# demod-breakout.net
KiCad netlist of a schematic drawn in EAGLE
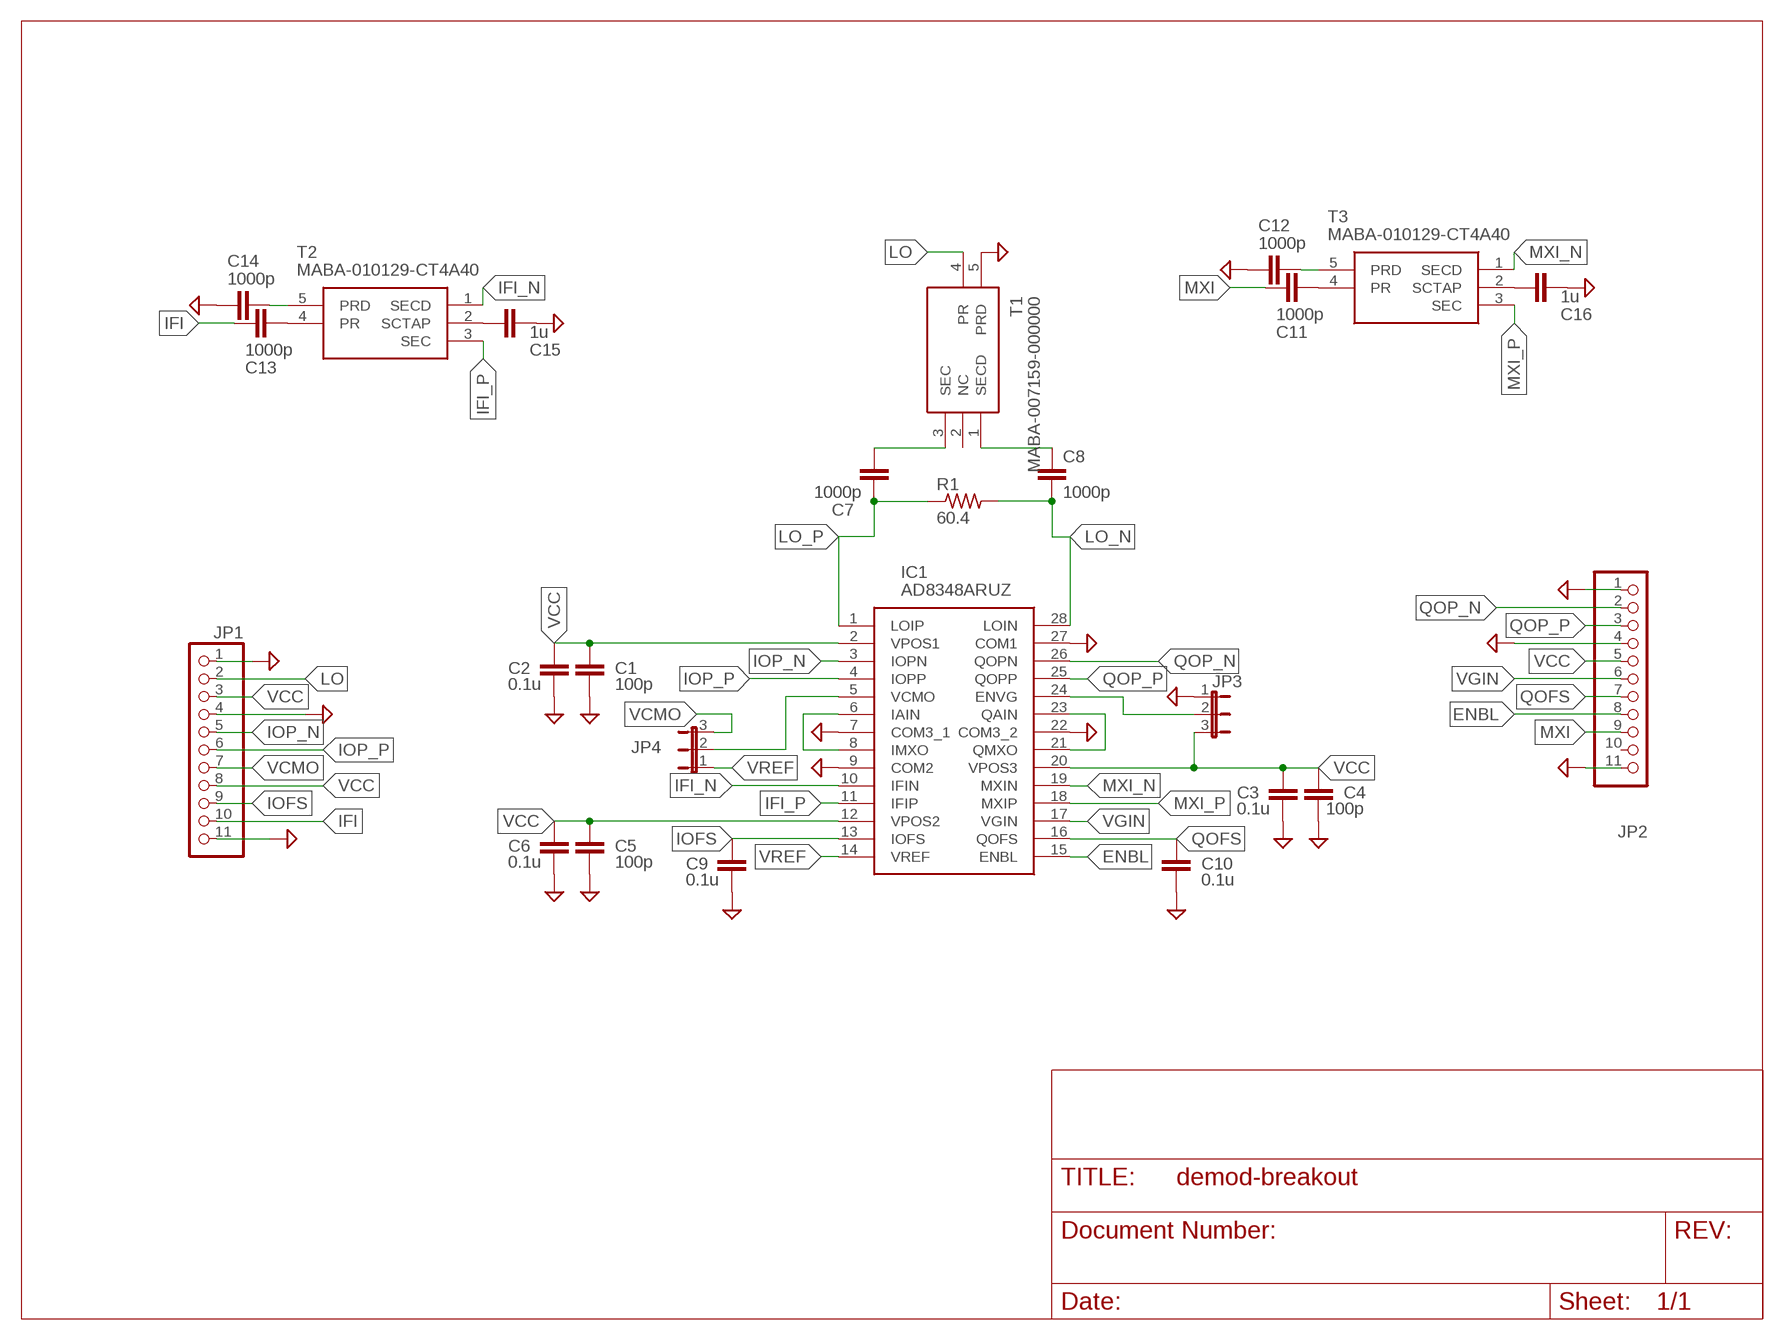
[diagram p0: schematic, sheet 1]

(export (version "E")
  (design (tool "Eeschema 10.0.6"))
  (components
    (comp (ref "C1")
      (value "100p")
      (footprint "eagle-import:C0402")
      (libsource (lib "eagle-import") (part "C-EUC0402"))
    )
    (comp (ref "C2")
      (value "0.1u")
      (footprint "eagle-import:C0402")
      (libsource (lib "eagle-import") (part "C-EUC0402"))
    )
    (comp (ref "C3")
      (value "0.1u")
      (footprint "eagle-import:C0402")
      (libsource (lib "eagle-import") (part "C-EUC0402"))
    )
    (comp (ref "C4")
      (value "100p")
      (footprint "eagle-import:C0402")
      (libsource (lib "eagle-import") (part "C-EUC0402"))
    )
    (comp (ref "C5")
      (value "100p")
      (footprint "eagle-import:C0402")
      (libsource (lib "eagle-import") (part "C-EUC0402"))
    )
    (comp (ref "C6")
      (value "0.1u")
      (footprint "eagle-import:C0402")
      (libsource (lib "eagle-import") (part "C-EUC0402"))
    )
    (comp (ref "C7")
      (value "1000p")
      (footprint "eagle-import:C0402")
      (libsource (lib "eagle-import") (part "C-EUC0402"))
    )
    (comp (ref "C8")
      (value "1000p")
      (footprint "eagle-import:C0402")
      (libsource (lib "eagle-import") (part "C-EUC0402"))
    )
    (comp (ref "C9")
      (value "0.1u")
      (footprint "eagle-import:C0402")
      (libsource (lib "eagle-import") (part "C-EUC0402"))
    )
    (comp (ref "C10")
      (value "0.1u")
      (footprint "eagle-import:C0402")
      (libsource (lib "eagle-import") (part "C-EUC0402"))
    )
    (comp (ref "C11")
      (value "1000p")
      (footprint "eagle-import:C0402")
      (libsource (lib "eagle-import") (part "C-EUC0402"))
    )
    (comp (ref "C12")
      (value "1000p")
      (footprint "eagle-import:C0402")
      (libsource (lib "eagle-import") (part "C-EUC0402"))
    )
    (comp (ref "C13")
      (value "1000p")
      (footprint "eagle-import:C0402")
      (libsource (lib "eagle-import") (part "C-EUC0402"))
    )
    (comp (ref "C14")
      (value "1000p")
      (footprint "eagle-import:C0402")
      (libsource (lib "eagle-import") (part "C-EUC0402"))
    )
    (comp (ref "C15")
      (value "1u")
      (footprint "eagle-import:C0603")
      (libsource (lib "eagle-import") (part "C-EUC0603"))
    )
    (comp (ref "C16")
      (value "1u")
      (footprint "eagle-import:C0603")
      (libsource (lib "eagle-import") (part "C-EUC0603"))
    )
    (comp (ref "IC1")
      (value "AD8348ARUZ")
      (footprint "eagle-import:SOP65P640X120-28N")
      (fields (field (name "MOUSER_PART_NUMBER") "584-AD8348ARUZ"))
      (libsource (lib "eagle-import") (part "AD8348ARUZ"))
    )
    (comp (ref "JP1")
      (value "PINHD-1X11")
      (footprint "eagle-import:1X11")
      (libsource (lib "eagle-import") (part "PINHD-1X11"))
    )
    (comp (ref "JP2")
      (value "PINHD-1X11")
      (footprint "eagle-import:1X11")
      (libsource (lib "eagle-import") (part "PINHD-1X11"))
    )
    (comp (ref "JP3")
      (value "VGA")
      (footprint "eagle-import:JP2")
      (libsource (lib "eagle-import") (part "JP2"))
    )
    (comp (ref "JP4")
      (value "VCMO")
      (footprint "eagle-import:JP2")
      (libsource (lib "eagle-import") (part "JP2"))
    )
    (comp (ref "R1")
      (value "60.4")
      (footprint "eagle-import:R0402")
      (libsource (lib "eagle-import") (part "R-US_R0402"))
    )
    (comp (ref "T1")
      (value "MABA-007159-000000")
      (footprint "eagle-import:E_SERIES_1")
      (fields (field (name "MOUSER_PART_NUMBER") "937-MABA007159000000"))
      (libsource (lib "eagle-import") (part "MABA-007159-000000"))
    )
    (comp (ref "T2")
      (value "MABA-010129-CT4A40")
      (footprint "eagle-import:MABA010129CT4A40")
      (fields (field (name "MOUSER_PART_NUMBER") "937-MABA010129CT4A40"))
      (libsource (lib "eagle-import") (part "MABA-010129-CT4A40"))
    )
    (comp (ref "T3")
      (value "MABA-010129-CT4A40")
      (footprint "eagle-import:MABA010129CT4A40")
      (fields (field (name "MOUSER_PART_NUMBER") "937-MABA010129CT4A40"))
      (libsource (lib "eagle-import") (part "MABA-010129-CT4A40"))
    )
  )
  (nets
    (net (code "1") (name "ENBL") (class "Default")
      (node (ref "IC1") (pin "15") (pinfunction "ENBL_15") (pintype "bidirectional"))
      (node (ref "JP2") (pin "8") (pinfunction "8_8") (pintype "passive"))
    )
    (net (code "2") (name "GND") (class "Default")
      (node (ref "C1") (pin "2") (pinfunction "2_2") (pintype "passive"))
      (node (ref "C10") (pin "2") (pinfunction "2_2") (pintype "passive"))
      (node (ref "C12") (pin "2") (pinfunction "2_2") (pintype "passive"))
      (node (ref "C14") (pin "2") (pinfunction "2_2") (pintype "passive"))
      (node (ref "C15") (pin "2") (pinfunction "2_2") (pintype "passive"))
      (node (ref "C16") (pin "2") (pinfunction "2_2") (pintype "passive"))
      (node (ref "C2") (pin "2") (pinfunction "2_2") (pintype "passive"))
      (node (ref "C3") (pin "2") (pinfunction "2_2") (pintype "passive"))
      (node (ref "C4") (pin "2") (pinfunction "2_2") (pintype "passive"))
      (node (ref "C5") (pin "2") (pinfunction "2_2") (pintype "passive"))
      (node (ref "C6") (pin "2") (pinfunction "2_2") (pintype "passive"))
      (node (ref "C9") (pin "2") (pinfunction "2_2") (pintype "passive"))
      (node (ref "IC1") (pin "22") (pinfunction "COM3_2_22") (pintype "bidirectional"))
      (node (ref "IC1") (pin "27") (pinfunction "COM1_27") (pintype "bidirectional"))
      (node (ref "IC1") (pin "7") (pinfunction "COM3_1_7") (pintype "bidirectional"))
      (node (ref "IC1") (pin "9") (pinfunction "COM2_9") (pintype "bidirectional"))
      (node (ref "JP1") (pin "1") (pinfunction "1_1") (pintype "passive"))
      (node (ref "JP1") (pin "11") (pinfunction "11_11") (pintype "passive"))
      (node (ref "JP1") (pin "4") (pinfunction "4_4") (pintype "passive"))
      (node (ref "JP2") (pin "1") (pinfunction "1_1") (pintype "passive"))
      (node (ref "JP2") (pin "11") (pinfunction "11_11") (pintype "passive"))
      (node (ref "JP2") (pin "4") (pinfunction "4_4") (pintype "passive"))
      (node (ref "JP3") (pin "1") (pinfunction "1_1") (pintype "passive"))
      (node (ref "T1") (pin "5") (pinfunction "PRD_5") (pintype "bidirectional"))
    )
    (net (code "3") (name "IFI") (class "Default")
      (node (ref "C13") (pin "1") (pinfunction "1_1") (pintype "passive"))
      (node (ref "JP1") (pin "10") (pinfunction "10_10") (pintype "passive"))
    )
    (net (code "4") (name "IFI_N") (class "Default")
      (node (ref "IC1") (pin "10") (pinfunction "IFIN_10") (pintype "bidirectional"))
      (node (ref "T2") (pin "1") (pinfunction "SECD_1") (pintype "bidirectional"))
    )
    (net (code "5") (name "IFI_P") (class "Default")
      (node (ref "IC1") (pin "11") (pinfunction "IFIP_11") (pintype "bidirectional"))
      (node (ref "T2") (pin "3") (pinfunction "SEC_3") (pintype "bidirectional"))
    )
    (net (code "6") (name "IOFS") (class "Default")
      (node (ref "C9") (pin "1") (pinfunction "1_1") (pintype "passive"))
      (node (ref "IC1") (pin "13") (pinfunction "IOFS_13") (pintype "bidirectional"))
      (node (ref "JP1") (pin "9") (pinfunction "9_9") (pintype "passive"))
    )
    (net (code "7") (name "IOP_N") (class "Default")
      (node (ref "IC1") (pin "3") (pinfunction "IOPN_3") (pintype "bidirectional"))
      (node (ref "JP1") (pin "5") (pinfunction "5_5") (pintype "passive"))
    )
    (net (code "8") (name "IOP_P") (class "Default")
      (node (ref "IC1") (pin "4") (pinfunction "IOPP_4") (pintype "bidirectional"))
      (node (ref "JP1") (pin "6") (pinfunction "6_6") (pintype "passive"))
    )
    (net (code "9") (name "LO") (class "Default")
      (node (ref "JP1") (pin "2") (pinfunction "2_2") (pintype "passive"))
      (node (ref "T1") (pin "4") (pinfunction "PR_4") (pintype "bidirectional"))
    )
    (net (code "10") (name "LO_N") (class "Default")
      (node (ref "C8") (pin "2") (pinfunction "2_2") (pintype "passive"))
      (node (ref "IC1") (pin "28") (pinfunction "LOIN_28") (pintype "bidirectional"))
      (node (ref "R1") (pin "2") (pinfunction "2_2") (pintype "passive"))
    )
    (net (code "11") (name "LO_P") (class "Default")
      (node (ref "C7") (pin "2") (pinfunction "2_2") (pintype "passive"))
      (node (ref "IC1") (pin "1") (pinfunction "LOIP_1") (pintype "bidirectional"))
      (node (ref "R1") (pin "1") (pinfunction "1_1") (pintype "passive"))
    )
    (net (code "12") (name "MXI") (class "Default")
      (node (ref "C11") (pin "1") (pinfunction "1_1") (pintype "passive"))
      (node (ref "JP2") (pin "9") (pinfunction "9_9") (pintype "passive"))
    )
    (net (code "13") (name "MXI_N") (class "Default")
      (node (ref "IC1") (pin "19") (pinfunction "MXIN_19") (pintype "bidirectional"))
      (node (ref "T3") (pin "1") (pinfunction "SECD_1") (pintype "bidirectional"))
    )
    (net (code "14") (name "MXI_P") (class "Default")
      (node (ref "IC1") (pin "18") (pinfunction "MXIP_18") (pintype "bidirectional"))
      (node (ref "T3") (pin "3") (pinfunction "SEC_3") (pintype "bidirectional"))
    )
    (net (code "15") (name "Net-(IC1-ENVG)") (class "Default")
      (node (ref "IC1") (pin "24") (pinfunction "ENVG_24") (pintype "bidirectional"))
      (node (ref "JP3") (pin "2") (pinfunction "2_2") (pintype "passive"))
    )
    (net (code "16") (name "Net-(IC1-IAIN)") (class "Default")
      (node (ref "IC1") (pin "6") (pinfunction "IAIN_6") (pintype "bidirectional"))
      (node (ref "IC1") (pin "8") (pinfunction "IMXO_8") (pintype "bidirectional"))
    )
    (net (code "17") (name "Net-(IC1-QAIN)") (class "Default")
      (node (ref "IC1") (pin "21") (pinfunction "QMXO_21") (pintype "bidirectional"))
      (node (ref "IC1") (pin "23") (pinfunction "QAIN_23") (pintype "bidirectional"))
    )
    (net (code "18") (name "Net-(IC1-VCMO)") (class "Default")
      (node (ref "IC1") (pin "5") (pinfunction "VCMO_5") (pintype "bidirectional"))
      (node (ref "JP4") (pin "2") (pinfunction "2_2") (pintype "passive"))
    )
    (net (code "19") (name "Net-(T1-SEC)") (class "Default")
      (node (ref "C7") (pin "1") (pinfunction "1_1") (pintype "passive"))
      (node (ref "T1") (pin "3") (pinfunction "SEC_3") (pintype "bidirectional"))
    )
    (net (code "20") (name "Net-(T1-SECD)") (class "Default")
      (node (ref "C8") (pin "1") (pinfunction "1_1") (pintype "passive"))
      (node (ref "T1") (pin "1") (pinfunction "SECD_1") (pintype "bidirectional"))
    )
    (net (code "21") (name "Net-(T2-PR)") (class "Default")
      (node (ref "C13") (pin "2") (pinfunction "2_2") (pintype "passive"))
      (node (ref "T2") (pin "4") (pinfunction "PR_4") (pintype "bidirectional"))
    )
    (net (code "22") (name "Net-(T2-PRD)") (class "Default")
      (node (ref "C14") (pin "1") (pinfunction "1_1") (pintype "passive"))
      (node (ref "T2") (pin "5") (pinfunction "PRD_5") (pintype "bidirectional"))
    )
    (net (code "23") (name "Net-(T2-SCTAP)") (class "Default")
      (node (ref "C15") (pin "1") (pinfunction "1_1") (pintype "passive"))
      (node (ref "T2") (pin "2") (pinfunction "SCTAP_2") (pintype "bidirectional"))
    )
    (net (code "24") (name "Net-(T3-PR)") (class "Default")
      (node (ref "C11") (pin "2") (pinfunction "2_2") (pintype "passive"))
      (node (ref "T3") (pin "4") (pinfunction "PR_4") (pintype "bidirectional"))
    )
    (net (code "25") (name "Net-(T3-PRD)") (class "Default")
      (node (ref "C12") (pin "1") (pinfunction "1_1") (pintype "passive"))
      (node (ref "T3") (pin "5") (pinfunction "PRD_5") (pintype "bidirectional"))
    )
    (net (code "26") (name "Net-(T3-SCTAP)") (class "Default")
      (node (ref "C16") (pin "1") (pinfunction "1_1") (pintype "passive"))
      (node (ref "T3") (pin "2") (pinfunction "SCTAP_2") (pintype "bidirectional"))
    )
    (net (code "27") (name "QOFS") (class "Default")
      (node (ref "C10") (pin "1") (pinfunction "1_1") (pintype "passive"))
      (node (ref "IC1") (pin "16") (pinfunction "QOFS_16") (pintype "bidirectional"))
      (node (ref "JP2") (pin "7") (pinfunction "7_7") (pintype "passive"))
    )
    (net (code "28") (name "QOP_N") (class "Default")
      (node (ref "IC1") (pin "26") (pinfunction "QOPN_26") (pintype "bidirectional"))
      (node (ref "JP2") (pin "2") (pinfunction "2_2") (pintype "passive"))
    )
    (net (code "29") (name "QOP_P") (class "Default")
      (node (ref "IC1") (pin "25") (pinfunction "QOPP_25") (pintype "bidirectional"))
      (node (ref "JP2") (pin "3") (pinfunction "3_3") (pintype "passive"))
    )
    (net (code "30") (name "VCC") (class "Default")
      (node (ref "C1") (pin "1") (pinfunction "1_1") (pintype "passive"))
      (node (ref "C2") (pin "1") (pinfunction "1_1") (pintype "passive"))
      (node (ref "C3") (pin "1") (pinfunction "1_1") (pintype "passive"))
      (node (ref "C4") (pin "1") (pinfunction "1_1") (pintype "passive"))
      (node (ref "C5") (pin "1") (pinfunction "1_1") (pintype "passive"))
      (node (ref "C6") (pin "1") (pinfunction "1_1") (pintype "passive"))
      (node (ref "IC1") (pin "12") (pinfunction "VPOS2_12") (pintype "bidirectional"))
      (node (ref "IC1") (pin "2") (pinfunction "VPOS1_2") (pintype "bidirectional"))
      (node (ref "IC1") (pin "20") (pinfunction "VPOS3_20") (pintype "bidirectional"))
      (node (ref "JP1") (pin "3") (pinfunction "3_3") (pintype "passive"))
      (node (ref "JP1") (pin "8") (pinfunction "8_8") (pintype "passive"))
      (node (ref "JP2") (pin "5") (pinfunction "5_5") (pintype "passive"))
      (node (ref "JP3") (pin "3") (pinfunction "3_3") (pintype "passive"))
    )
    (net (code "31") (name "VCMO") (class "Default")
      (node (ref "JP1") (pin "7") (pinfunction "7_7") (pintype "passive"))
      (node (ref "JP4") (pin "3") (pinfunction "3_3") (pintype "passive"))
    )
    (net (code "32") (name "VGIN") (class "Default")
      (node (ref "IC1") (pin "17") (pinfunction "VGIN_17") (pintype "bidirectional"))
      (node (ref "JP2") (pin "6") (pinfunction "6_6") (pintype "passive"))
    )
    (net (code "33") (name "VREF") (class "Default")
      (node (ref "IC1") (pin "14") (pinfunction "VREF_14") (pintype "bidirectional"))
      (node (ref "JP4") (pin "1") (pinfunction "1_1") (pintype "passive"))
    )
    (net (code "34") (name "unconnected-(JP2-Pad10)") (class "Default")
      (node (ref "JP2") (pin "10") (pinfunction "10_10") (pintype "passive"))
    )
    (net (code "35") (name "unconnected-(T1-NC-Pad2)") (class "Default")
      (node (ref "T1") (pin "2") (pinfunction "NC_2") (pintype "no_connect"))
    )
  )
)
